# AudioTest.net
KiCad netlist of a schematic drawn in EAGLE
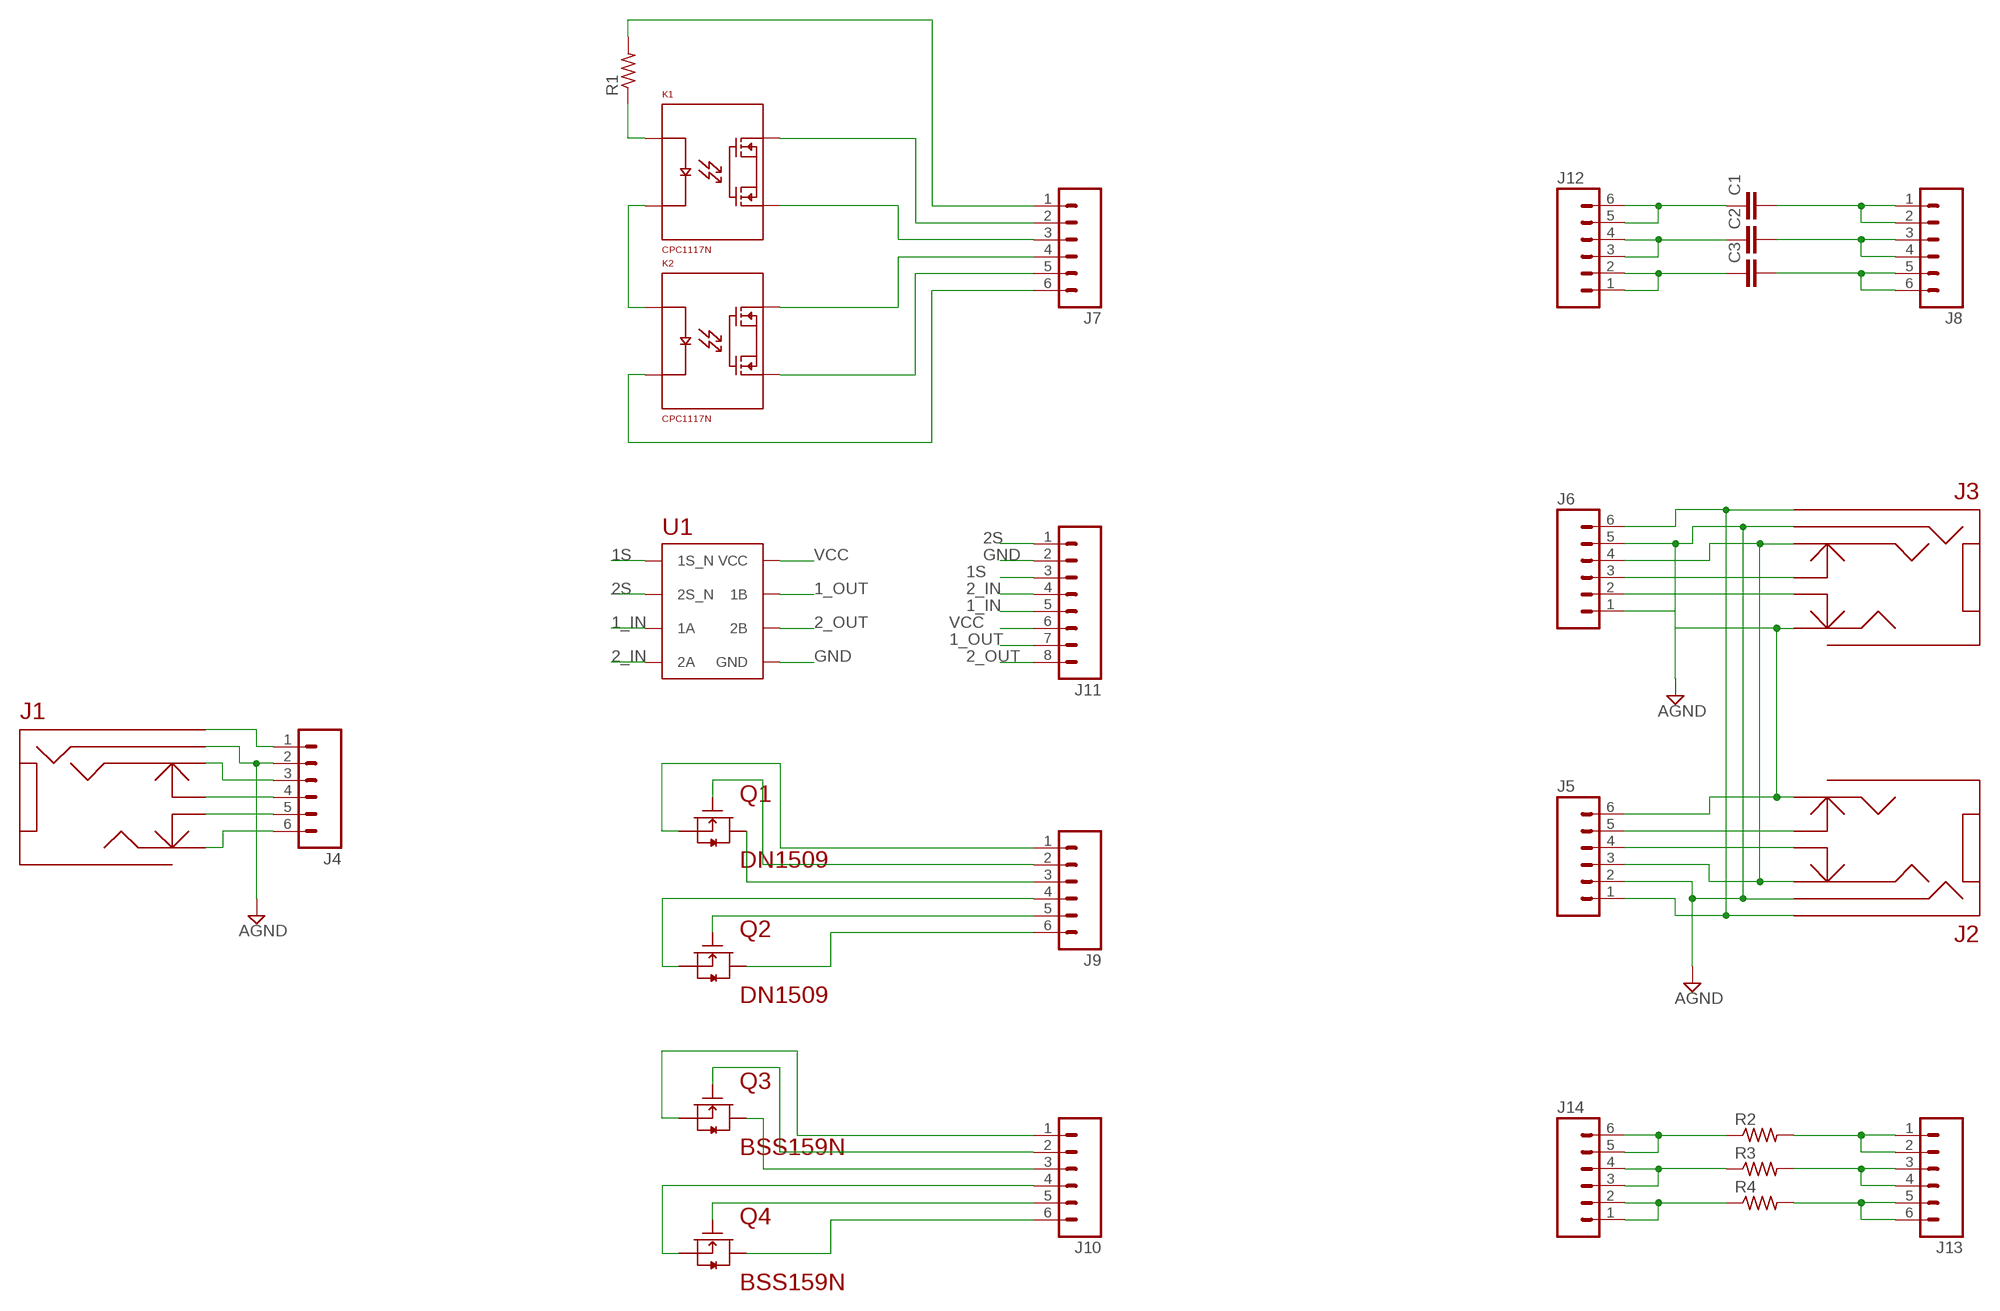
[diagram p0: schematic, sheet 1]

(export (version "E")
  (design (tool "Eeschema 10.0.6"))
  (components
    (comp (ref "C1")
      (value "C-EUC1210")
      (footprint "eagle-import:C1210")
      (libsource (lib "eagle-import") (part "C-EUC1210"))
    )
    (comp (ref "C2")
      (value "C-EUC1210")
      (footprint "eagle-import:C1210")
      (libsource (lib "eagle-import") (part "C-EUC1210"))
    )
    (comp (ref "C3")
      (value "C-EUC1210")
      (footprint "eagle-import:C1210")
      (libsource (lib "eagle-import") (part "C-EUC1210"))
    )
    (comp (ref "J1")
      (value "SJ-43516")
      (footprint "eagle-import:SJ-43516-SMT")
      (libsource (lib "eagle-import") (part "SJ-43516"))
    )
    (comp (ref "J2")
      (value "SJ-43516")
      (footprint "eagle-import:SJ-43516-SMT")
      (libsource (lib "eagle-import") (part "SJ-43516"))
    )
    (comp (ref "J3")
      (value "SJ-43516")
      (footprint "eagle-import:SJ-43516-SMT")
      (libsource (lib "eagle-import") (part "SJ-43516"))
    )
    (comp (ref "J4")
      (value "M06LOCK")
      (footprint "eagle-import:1X06_LOCK")
      (libsource (lib "eagle-import") (part "M06LOCK"))
    )
    (comp (ref "J5")
      (value "M06LOCK")
      (footprint "eagle-import:1X06_LOCK")
      (libsource (lib "eagle-import") (part "M06LOCK"))
    )
    (comp (ref "J6")
      (value "M06LOCK")
      (footprint "eagle-import:1X06_LOCK")
      (libsource (lib "eagle-import") (part "M06LOCK"))
    )
    (comp (ref "J7")
      (value "M06LOCK")
      (footprint "eagle-import:1X06_LOCK")
      (libsource (lib "eagle-import") (part "M06LOCK"))
    )
    (comp (ref "J8")
      (value "M06LOCK")
      (footprint "eagle-import:1X06_LOCK")
      (libsource (lib "eagle-import") (part "M06LOCK"))
    )
    (comp (ref "J9")
      (value "M06LOCK")
      (footprint "eagle-import:1X06_LOCK")
      (libsource (lib "eagle-import") (part "M06LOCK"))
    )
    (comp (ref "J10")
      (value "M06LOCK")
      (footprint "eagle-import:1X06_LOCK")
      (libsource (lib "eagle-import") (part "M06LOCK"))
    )
    (comp (ref "J11")
      (value "M08LOCK")
      (footprint "eagle-import:1X08_LOCK")
      (libsource (lib "eagle-import") (part "M08LOCK"))
    )
    (comp (ref "J12")
      (value "M06LOCK")
      (footprint "eagle-import:1X06_LOCK")
      (libsource (lib "eagle-import") (part "M06LOCK"))
    )
    (comp (ref "J13")
      (value "M06LOCK")
      (footprint "eagle-import:1X06_LOCK")
      (libsource (lib "eagle-import") (part "M06LOCK"))
    )
    (comp (ref "J14")
      (value "M06LOCK")
      (footprint "eagle-import:1X06_LOCK")
      (libsource (lib "eagle-import") (part "M06LOCK"))
    )
    (comp (ref "K1")
      (value "CPC1117N")
      (footprint "eagle-import:4-SOP")
      (libsource (lib "eagle-import") (part "CPC1117N"))
    )
    (comp (ref "K2")
      (value "CPC1117N")
      (footprint "eagle-import:4-SOP")
      (libsource (lib "eagle-import") (part "CPC1117N"))
    )
    (comp (ref "Q1")
      (value "DN1509")
      (footprint "eagle-import:SOT-23-5")
      (libsource (lib "eagle-import") (part "DN1509"))
    )
    (comp (ref "Q2")
      (value "DN1509")
      (footprint "eagle-import:SOT-23-5")
      (libsource (lib "eagle-import") (part "DN1509"))
    )
    (comp (ref "Q3")
      (value "BSS159N")
      (footprint "eagle-import:SOT-23-3")
      (libsource (lib "eagle-import") (part "BSS159N"))
    )
    (comp (ref "Q4")
      (value "BSS159N")
      (footprint "eagle-import:SOT-23-3")
      (libsource (lib "eagle-import") (part "BSS159N"))
    )
    (comp (ref "R1")
      (value "R-US_R0805")
      (footprint "eagle-import:R0805")
      (libsource (lib "eagle-import") (part "R-US_R0805"))
    )
    (comp (ref "R2")
      (value "R-US_M0805")
      (footprint "eagle-import:M0805")
      (libsource (lib "eagle-import") (part "R-US_M0805"))
    )
    (comp (ref "R3")
      (value "R-US_M0805")
      (footprint "eagle-import:M0805")
      (libsource (lib "eagle-import") (part "R-US_M0805"))
    )
    (comp (ref "R4")
      (value "R-US_M0805")
      (footprint "eagle-import:M0805")
      (libsource (lib "eagle-import") (part "R-US_M0805"))
    )
    (comp (ref "U1")
      (value "FSA553")
      (footprint "eagle-import:9-UFBGA-NSMD")
      (libsource (lib "eagle-import") (part "FSA553"))
    )
  )
  (nets
    (net (code "1") (name "/1S") (class "Default")
      (node (ref "J11") (pin "3") (pinfunction "3_3") (pintype "passive"))
      (node (ref "U1") (pin "C1") (pinfunction "1S_N_C1") (pintype "bidirectional"))
    )
    (net (code "2") (name "/1_IN") (class "Default")
      (node (ref "J11") (pin "5") (pinfunction "5_5") (pintype "passive"))
      (node (ref "U1") (pin "A1") (pinfunction "1A_A1") (pintype "bidirectional"))
    )
    (net (code "3") (name "/1_OUT") (class "Default")
      (node (ref "J11") (pin "7") (pinfunction "7_7") (pintype "passive"))
      (node (ref "U1") (pin "A3") (pinfunction "1B_A3") (pintype "bidirectional"))
    )
    (net (code "4") (name "/2S") (class "Default")
      (node (ref "J11") (pin "1") (pinfunction "1_1") (pintype "passive"))
      (node (ref "U1") (pin "C3") (pinfunction "2S_N_C3") (pintype "bidirectional"))
    )
    (net (code "5") (name "/2_IN") (class "Default")
      (node (ref "J11") (pin "4") (pinfunction "4_4") (pintype "passive"))
      (node (ref "U1") (pin "B1") (pinfunction "2A_B1") (pintype "bidirectional"))
    )
    (net (code "6") (name "/2_OUT") (class "Default")
      (node (ref "J11") (pin "8") (pinfunction "8_8") (pintype "passive"))
      (node (ref "U1") (pin "B3") (pinfunction "2B_B3") (pintype "bidirectional"))
    )
    (net (code "7") (name "/GND") (class "Default")
      (node (ref "J11") (pin "2") (pinfunction "2_2") (pintype "passive"))
      (node (ref "U1") (pin "C2") (pinfunction "GND_C2") (pintype "bidirectional"))
    )
    (net (code "8") (name "/VCC") (class "Default")
      (node (ref "J11") (pin "6") (pinfunction "6_6") (pintype "passive"))
      (node (ref "U1") (pin "A2") (pinfunction "VCC_A2") (pintype "bidirectional"))
    )
    (net (code "9") (name "AGND") (class "Default")
      (node (ref "J1") (pin "4") (pinfunction "GND_4") (pintype "bidirectional"))
      (node (ref "J2") (pin "4") (pinfunction "GND_4") (pintype "bidirectional"))
      (node (ref "J3") (pin "4") (pinfunction "GND_4") (pintype "bidirectional"))
      (node (ref "J4") (pin "2") (pinfunction "2_2") (pintype "passive"))
      (node (ref "J5") (pin "2") (pinfunction "2_2") (pintype "passive"))
      (node (ref "J6") (pin "5") (pinfunction "5_5") (pintype "passive"))
    )
    (net (code "10") (name "Net-(C1-Pad1)") (class "Default")
      (node (ref "C1") (pin "1") (pinfunction "1_1") (pintype "passive"))
      (node (ref "J12") (pin "5") (pinfunction "5_5") (pintype "passive"))
      (node (ref "J12") (pin "6") (pinfunction "6_6") (pintype "passive"))
    )
    (net (code "11") (name "Net-(C1-Pad2)") (class "Default")
      (node (ref "C1") (pin "2") (pinfunction "2_2") (pintype "passive"))
      (node (ref "J8") (pin "1") (pinfunction "1_1") (pintype "passive"))
      (node (ref "J8") (pin "2") (pinfunction "2_2") (pintype "passive"))
    )
    (net (code "12") (name "Net-(C2-Pad1)") (class "Default")
      (node (ref "C2") (pin "1") (pinfunction "1_1") (pintype "passive"))
      (node (ref "J12") (pin "3") (pinfunction "3_3") (pintype "passive"))
      (node (ref "J12") (pin "4") (pinfunction "4_4") (pintype "passive"))
    )
    (net (code "13") (name "Net-(C2-Pad2)") (class "Default")
      (node (ref "C2") (pin "2") (pinfunction "2_2") (pintype "passive"))
      (node (ref "J8") (pin "3") (pinfunction "3_3") (pintype "passive"))
      (node (ref "J8") (pin "4") (pinfunction "4_4") (pintype "passive"))
    )
    (net (code "14") (name "Net-(C3-Pad1)") (class "Default")
      (node (ref "C3") (pin "1") (pinfunction "1_1") (pintype "passive"))
      (node (ref "J12") (pin "1") (pinfunction "1_1") (pintype "passive"))
      (node (ref "J12") (pin "2") (pinfunction "2_2") (pintype "passive"))
    )
    (net (code "15") (name "Net-(C3-Pad2)") (class "Default")
      (node (ref "C3") (pin "2") (pinfunction "2_2") (pintype "passive"))
      (node (ref "J8") (pin "5") (pinfunction "5_5") (pintype "passive"))
      (node (ref "J8") (pin "6") (pinfunction "6_6") (pintype "passive"))
    )
    (net (code "16") (name "Net-(J1-LEFT)") (class "Default")
      (node (ref "J1") (pin "2") (pinfunction "LEFT_2") (pintype "bidirectional"))
      (node (ref "J4") (pin "6") (pinfunction "6_6") (pintype "passive"))
    )
    (net (code "17") (name "Net-(J1-LEFT_NC)") (class "Default")
      (node (ref "J1") (pin "5") (pinfunction "LEFT_NC_5") (pintype "bidirectional"))
      (node (ref "J4") (pin "5") (pinfunction "5_5") (pintype "passive"))
    )
    (net (code "18") (name "Net-(J1-MIC)") (class "Default")
      (node (ref "J1") (pin "1") (pinfunction "MIC_1") (pintype "bidirectional"))
      (node (ref "J4") (pin "1") (pinfunction "1_1") (pintype "passive"))
    )
    (net (code "19") (name "Net-(J1-RIGHT)") (class "Default")
      (node (ref "J1") (pin "3") (pinfunction "RIGHT_3") (pintype "bidirectional"))
      (node (ref "J4") (pin "3") (pinfunction "3_3") (pintype "passive"))
    )
    (net (code "20") (name "Net-(J1-RIGHT_NC)") (class "Default")
      (node (ref "J1") (pin "6") (pinfunction "RIGHT_NC_6") (pintype "bidirectional"))
      (node (ref "J4") (pin "4") (pinfunction "4_4") (pintype "passive"))
    )
    (net (code "21") (name "Net-(J2-LEFT)") (class "Default")
      (node (ref "J2") (pin "2") (pinfunction "LEFT_2") (pintype "bidirectional"))
      (node (ref "J3") (pin "2") (pinfunction "LEFT_2") (pintype "bidirectional"))
      (node (ref "J5") (pin "6") (pinfunction "6_6") (pintype "passive"))
      (node (ref "J6") (pin "1") (pinfunction "1_1") (pintype "passive"))
    )
    (net (code "22") (name "Net-(J2-LEFT_NC)") (class "Default")
      (node (ref "J2") (pin "5") (pinfunction "LEFT_NC_5") (pintype "bidirectional"))
      (node (ref "J5") (pin "5") (pinfunction "5_5") (pintype "passive"))
    )
    (net (code "23") (name "Net-(J2-MIC)") (class "Default")
      (node (ref "J2") (pin "1") (pinfunction "MIC_1") (pintype "bidirectional"))
      (node (ref "J3") (pin "1") (pinfunction "MIC_1") (pintype "bidirectional"))
      (node (ref "J5") (pin "1") (pinfunction "1_1") (pintype "passive"))
      (node (ref "J6") (pin "6") (pinfunction "6_6") (pintype "passive"))
    )
    (net (code "24") (name "Net-(J2-RIGHT)") (class "Default")
      (node (ref "J2") (pin "3") (pinfunction "RIGHT_3") (pintype "bidirectional"))
      (node (ref "J3") (pin "3") (pinfunction "RIGHT_3") (pintype "bidirectional"))
      (node (ref "J5") (pin "3") (pinfunction "3_3") (pintype "passive"))
      (node (ref "J6") (pin "4") (pinfunction "4_4") (pintype "passive"))
    )
    (net (code "25") (name "Net-(J2-RIGHT_NC)") (class "Default")
      (node (ref "J2") (pin "6") (pinfunction "RIGHT_NC_6") (pintype "bidirectional"))
      (node (ref "J5") (pin "4") (pinfunction "4_4") (pintype "passive"))
    )
    (net (code "26") (name "Net-(J3-LEFT_NC)") (class "Default")
      (node (ref "J3") (pin "5") (pinfunction "LEFT_NC_5") (pintype "bidirectional"))
      (node (ref "J6") (pin "2") (pinfunction "2_2") (pintype "passive"))
    )
    (net (code "27") (name "Net-(J3-RIGHT_NC)") (class "Default")
      (node (ref "J3") (pin "6") (pinfunction "RIGHT_NC_6") (pintype "bidirectional"))
      (node (ref "J6") (pin "3") (pinfunction "3_3") (pintype "passive"))
    )
    (net (code "28") (name "Net-(J7-Pad1)") (class "Default")
      (node (ref "J7") (pin "1") (pinfunction "1_1") (pintype "passive"))
      (node (ref "R1") (pin "2") (pinfunction "2_2") (pintype "passive"))
    )
    (net (code "29") (name "Net-(J13-Pad1)") (class "Default")
      (node (ref "J13") (pin "1") (pinfunction "1_1") (pintype "passive"))
      (node (ref "J13") (pin "2") (pinfunction "2_2") (pintype "passive"))
      (node (ref "R2") (pin "2") (pinfunction "2_2") (pintype "passive"))
    )
    (net (code "30") (name "Net-(J13-Pad3)") (class "Default")
      (node (ref "J13") (pin "3") (pinfunction "3_3") (pintype "passive"))
      (node (ref "J13") (pin "4") (pinfunction "4_4") (pintype "passive"))
      (node (ref "R3") (pin "2") (pinfunction "2_2") (pintype "passive"))
    )
    (net (code "31") (name "Net-(J13-Pad5)") (class "Default")
      (node (ref "J13") (pin "5") (pinfunction "5_5") (pintype "passive"))
      (node (ref "J13") (pin "6") (pinfunction "6_6") (pintype "passive"))
      (node (ref "R4") (pin "2") (pinfunction "2_2") (pintype "passive"))
    )
    (net (code "32") (name "Net-(J14-Pad1)") (class "Default")
      (node (ref "J14") (pin "1") (pinfunction "1_1") (pintype "passive"))
      (node (ref "J14") (pin "2") (pinfunction "2_2") (pintype "passive"))
      (node (ref "R4") (pin "1") (pinfunction "1_1") (pintype "passive"))
    )
    (net (code "33") (name "Net-(J14-Pad3)") (class "Default")
      (node (ref "J14") (pin "3") (pinfunction "3_3") (pintype "passive"))
      (node (ref "J14") (pin "4") (pinfunction "4_4") (pintype "passive"))
      (node (ref "R3") (pin "1") (pinfunction "1_1") (pintype "passive"))
    )
    (net (code "34") (name "Net-(J14-Pad5)") (class "Default")
      (node (ref "J14") (pin "5") (pinfunction "5_5") (pintype "passive"))
      (node (ref "J14") (pin "6") (pinfunction "6_6") (pintype "passive"))
      (node (ref "R2") (pin "1") (pinfunction "1_1") (pintype "passive"))
    )
    (net (code "35") (name "Net-(K1-A)") (class "Default")
      (node (ref "K1") (pin "1") (pinfunction "A_1") (pintype "bidirectional"))
      (node (ref "R1") (pin "1") (pinfunction "1_1") (pintype "passive"))
    )
    (net (code "36") (name "Net-(K1-C)") (class "Default")
      (node (ref "K1") (pin "2") (pinfunction "C_2") (pintype "bidirectional"))
      (node (ref "K2") (pin "1") (pinfunction "A_1") (pintype "bidirectional"))
    )
    (net (code "37") (name "Net-(K1-LOAD1)") (class "Default")
      (node (ref "J7") (pin "2") (pinfunction "2_2") (pintype "passive"))
      (node (ref "K1") (pin "4") (pinfunction "LOAD1_4") (pintype "bidirectional"))
    )
    (net (code "38") (name "Net-(K1-LOAD2)") (class "Default")
      (node (ref "J7") (pin "3") (pinfunction "3_3") (pintype "passive"))
      (node (ref "K1") (pin "3") (pinfunction "LOAD2_3") (pintype "bidirectional"))
    )
    (net (code "39") (name "Net-(K2-C)") (class "Default")
      (node (ref "J7") (pin "6") (pinfunction "6_6") (pintype "passive"))
      (node (ref "K2") (pin "2") (pinfunction "C_2") (pintype "bidirectional"))
    )
    (net (code "40") (name "Net-(K2-LOAD1)") (class "Default")
      (node (ref "J7") (pin "4") (pinfunction "4_4") (pintype "passive"))
      (node (ref "K2") (pin "4") (pinfunction "LOAD1_4") (pintype "bidirectional"))
    )
    (net (code "41") (name "Net-(K2-LOAD2)") (class "Default")
      (node (ref "J7") (pin "5") (pinfunction "5_5") (pintype "passive"))
      (node (ref "K2") (pin "3") (pinfunction "LOAD2_3") (pintype "bidirectional"))
    )
    (net (code "42") (name "Net-(Q1-D)") (class "Default")
      (node (ref "J9") (pin "3") (pinfunction "3_3") (pintype "passive"))
      (node (ref "Q1") (pin "2") (pinfunction "D_2") (pintype "bidirectional"))
    )
    (net (code "43") (name "Net-(Q1-G)") (class "Default")
      (node (ref "J9") (pin "2") (pinfunction "2_2") (pintype "passive"))
      (node (ref "Q1") (pin "5") (pinfunction "G_5") (pintype "bidirectional"))
    )
    (net (code "44") (name "Net-(Q1-S)") (class "Default")
      (node (ref "J9") (pin "1") (pinfunction "1_1") (pintype "passive"))
      (node (ref "Q1") (pin "4") (pinfunction "S_4") (pintype "bidirectional"))
    )
    (net (code "45") (name "Net-(Q2-D)") (class "Default")
      (node (ref "J9") (pin "6") (pinfunction "6_6") (pintype "passive"))
      (node (ref "Q2") (pin "2") (pinfunction "D_2") (pintype "bidirectional"))
    )
    (net (code "46") (name "Net-(Q2-G)") (class "Default")
      (node (ref "J9") (pin "5") (pinfunction "5_5") (pintype "passive"))
      (node (ref "Q2") (pin "5") (pinfunction "G_5") (pintype "bidirectional"))
    )
    (net (code "47") (name "Net-(Q2-S)") (class "Default")
      (node (ref "J9") (pin "4") (pinfunction "4_4") (pintype "passive"))
      (node (ref "Q2") (pin "4") (pinfunction "S_4") (pintype "bidirectional"))
    )
    (net (code "48") (name "Net-(Q3-D)") (class "Default")
      (node (ref "J10") (pin "3") (pinfunction "3_3") (pintype "passive"))
      (node (ref "Q3") (pin "3") (pinfunction "D_3") (pintype "bidirectional"))
    )
    (net (code "49") (name "Net-(Q3-G)") (class "Default")
      (node (ref "J10") (pin "2") (pinfunction "2_2") (pintype "passive"))
      (node (ref "Q3") (pin "1") (pinfunction "G_1") (pintype "bidirectional"))
    )
    (net (code "50") (name "Net-(Q3-S)") (class "Default")
      (node (ref "J10") (pin "1") (pinfunction "1_1") (pintype "passive"))
      (node (ref "Q3") (pin "2") (pinfunction "S_2") (pintype "bidirectional"))
    )
    (net (code "51") (name "Net-(Q4-D)") (class "Default")
      (node (ref "J10") (pin "6") (pinfunction "6_6") (pintype "passive"))
      (node (ref "Q4") (pin "3") (pinfunction "D_3") (pintype "bidirectional"))
    )
    (net (code "52") (name "Net-(Q4-G)") (class "Default")
      (node (ref "J10") (pin "5") (pinfunction "5_5") (pintype "passive"))
      (node (ref "Q4") (pin "1") (pinfunction "G_1") (pintype "bidirectional"))
    )
    (net (code "53") (name "Net-(Q4-S)") (class "Default")
      (node (ref "J10") (pin "4") (pinfunction "4_4") (pintype "passive"))
      (node (ref "Q4") (pin "2") (pinfunction "S_2") (pintype "bidirectional"))
    )
  )
)
